# PT4115.net
KiCad netlist of a schematic drawn in EAGLE
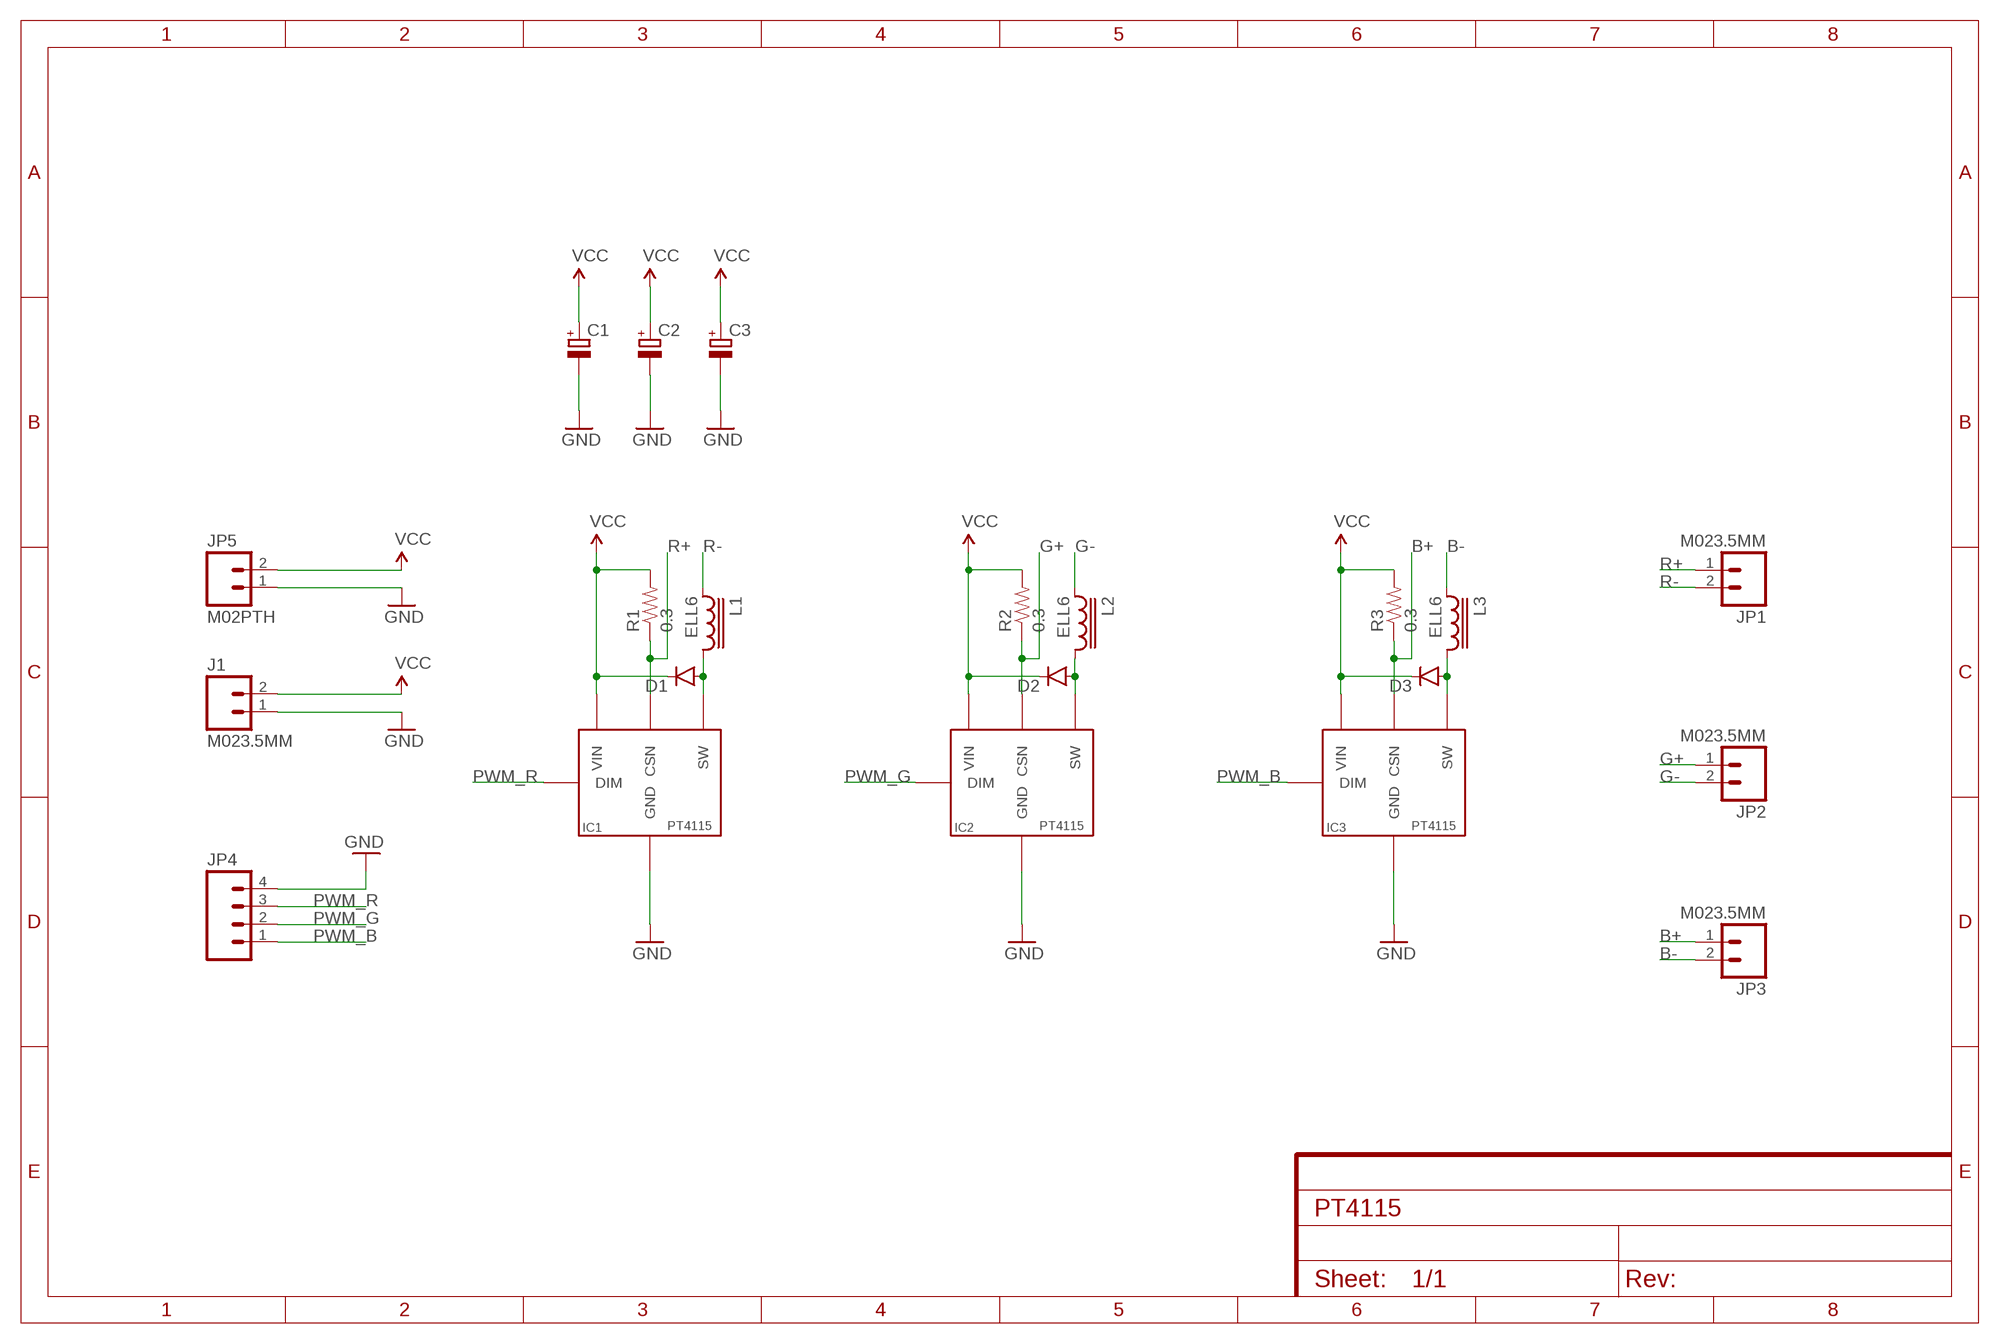
[diagram p0: schematic, sheet 1]

(export (version "E")
  (design (tool "Eeschema 10.0.6"))
  (components
    (comp (ref "C1")
      (value "CPOL-EUD/7343-31R")
      (footprint "eagle-import:D_7343-31R")
      (libsource (lib "eagle-import") (part "CPOL-EUD/7343-31R"))
    )
    (comp (ref "C2")
      (value "CPOL-EUD/7343-31R")
      (footprint "eagle-import:D_7343-31R")
      (libsource (lib "eagle-import") (part "CPOL-EUD/7343-31R"))
    )
    (comp (ref "C3")
      (value "CPOL-EUD/7343-31R")
      (footprint "eagle-import:D_7343-31R")
      (libsource (lib "eagle-import") (part "CPOL-EUD/7343-31R"))
    )
    (comp (ref "D1")
      (value "DIODESMA-KIT")
      (footprint "eagle-import:SMA-DIODE-KIT")
      (libsource (lib "eagle-import") (part "DIODESMA-KIT"))
    )
    (comp (ref "D2")
      (value "DIODESMA-KIT")
      (footprint "eagle-import:SMA-DIODE-KIT")
      (libsource (lib "eagle-import") (part "DIODESMA-KIT"))
    )
    (comp (ref "D3")
      (value "DIODESMA-KIT")
      (footprint "eagle-import:SMA-DIODE-KIT")
      (libsource (lib "eagle-import") (part "DIODESMA-KIT"))
    )
    (comp (ref "IC1")
      (value "PT4115PT4115B89E")
      (footprint "eagle-import:SOT89-5")
      (libsource (lib "eagle-import") (part "PT4115PT4115B89E"))
    )
    (comp (ref "IC2")
      (value "PT4115PT4115B89E")
      (footprint "eagle-import:SOT89-5")
      (libsource (lib "eagle-import") (part "PT4115PT4115B89E"))
    )
    (comp (ref "IC3")
      (value "PT4115PT4115B89E")
      (footprint "eagle-import:SOT89-5")
      (libsource (lib "eagle-import") (part "PT4115PT4115B89E"))
    )
    (comp (ref "J1")
      (value "M023.5MM")
      (footprint "eagle-import:SCREWTERMINAL-3.5MM-2")
      (libsource (lib "eagle-import") (part "M023.5MM"))
    )
    (comp (ref "JP1")
      (value "M023.5MM")
      (footprint "eagle-import:SCREWTERMINAL-3.5MM-2")
      (libsource (lib "eagle-import") (part "M023.5MM"))
    )
    (comp (ref "JP2")
      (value "M023.5MM")
      (footprint "eagle-import:SCREWTERMINAL-3.5MM-2")
      (libsource (lib "eagle-import") (part "M023.5MM"))
    )
    (comp (ref "JP3")
      (value "M023.5MM")
      (footprint "eagle-import:SCREWTERMINAL-3.5MM-2")
      (libsource (lib "eagle-import") (part "M023.5MM"))
    )
    (comp (ref "JP4")
      (value "M04LONGPADS")
      (footprint "eagle-import:1X04_LONGPADS")
      (libsource (lib "eagle-import") (part "M04LONGPADS"))
    )
    (comp (ref "JP5")
      (value "M02PTH")
      (footprint "eagle-import:1X02")
      (libsource (lib "eagle-import") (part "M02PTH"))
    )
    (comp (ref "L1")
      (value "ELL6")
      (footprint "eagle-import:ELL6")
      (libsource (lib "eagle-import") (part "ELL6"))
    )
    (comp (ref "L2")
      (value "ELL6")
      (footprint "eagle-import:ELL6")
      (libsource (lib "eagle-import") (part "ELL6"))
    )
    (comp (ref "L3")
      (value "ELL6")
      (footprint "eagle-import:ELL6")
      (libsource (lib "eagle-import") (part "ELL6"))
    )
    (comp (ref "R1")
      (value "0.3")
      (footprint "eagle-import:0805")
      (libsource (lib "eagle-import") (part "0.3OHM-1/8W-1%(0805)"))
    )
    (comp (ref "R2")
      (value "0.3")
      (footprint "eagle-import:0805")
      (libsource (lib "eagle-import") (part "0.3OHM-1/8W-1%(0805)"))
    )
    (comp (ref "R3")
      (value "0.3")
      (footprint "eagle-import:0805")
      (libsource (lib "eagle-import") (part "0.3OHM-1/8W-1%(0805)"))
    )
  )
  (nets
    (net (code "1") (name "/B+") (class "Default")
      (node (ref "IC3") (pin "4") (pinfunction "CSN_4") (pintype "bidirectional"))
      (node (ref "JP3") (pin "1") (pinfunction "1_1") (pintype "passive"))
      (node (ref "R3") (pin "1") (pinfunction "1_1") (pintype "passive"))
    )
    (net (code "2") (name "/B-") (class "Default")
      (node (ref "JP3") (pin "2") (pinfunction "2_2") (pintype "passive"))
      (node (ref "L3") (pin "1") (pinfunction "1_1") (pintype "passive"))
    )
    (net (code "3") (name "/G+") (class "Default")
      (node (ref "IC2") (pin "4") (pinfunction "CSN_4") (pintype "bidirectional"))
      (node (ref "JP2") (pin "1") (pinfunction "1_1") (pintype "passive"))
      (node (ref "R2") (pin "1") (pinfunction "1_1") (pintype "passive"))
    )
    (net (code "4") (name "/G-") (class "Default")
      (node (ref "JP2") (pin "2") (pinfunction "2_2") (pintype "passive"))
      (node (ref "L2") (pin "1") (pinfunction "1_1") (pintype "passive"))
    )
    (net (code "5") (name "/PWM_B") (class "Default")
      (node (ref "IC3") (pin "3") (pinfunction "DIM_3") (pintype "bidirectional"))
      (node (ref "JP4") (pin "1") (pinfunction "1_1") (pintype "passive"))
    )
    (net (code "6") (name "/PWM_G") (class "Default")
      (node (ref "IC2") (pin "3") (pinfunction "DIM_3") (pintype "bidirectional"))
      (node (ref "JP4") (pin "2") (pinfunction "2_2") (pintype "passive"))
    )
    (net (code "7") (name "/PWM_R") (class "Default")
      (node (ref "IC1") (pin "3") (pinfunction "DIM_3") (pintype "bidirectional"))
      (node (ref "JP4") (pin "3") (pinfunction "3_3") (pintype "passive"))
    )
    (net (code "8") (name "/R+") (class "Default")
      (node (ref "IC1") (pin "4") (pinfunction "CSN_4") (pintype "bidirectional"))
      (node (ref "JP1") (pin "1") (pinfunction "1_1") (pintype "passive"))
      (node (ref "R1") (pin "1") (pinfunction "1_1") (pintype "passive"))
    )
    (net (code "9") (name "/R-") (class "Default")
      (node (ref "JP1") (pin "2") (pinfunction "2_2") (pintype "passive"))
      (node (ref "L1") (pin "1") (pinfunction "1_1") (pintype "passive"))
    )
    (net (code "10") (name "GND") (class "Default")
      (node (ref "C1") (pin "-") (pinfunction "-_-") (pintype "passive"))
      (node (ref "C2") (pin "-") (pinfunction "-_-") (pintype "passive"))
      (node (ref "C3") (pin "-") (pinfunction "-_-") (pintype "passive"))
      (node (ref "IC1") (pin "2") (pinfunction "GND_2") (pintype "power_in"))
      (node (ref "IC1") (pin "2A") (pinfunction "GND_2A") (pintype "power_in"))
      (node (ref "IC2") (pin "2") (pinfunction "GND_2") (pintype "power_in"))
      (node (ref "IC2") (pin "2A") (pinfunction "GND_2A") (pintype "power_in"))
      (node (ref "IC3") (pin "2") (pinfunction "GND_2") (pintype "power_in"))
      (node (ref "IC3") (pin "2A") (pinfunction "GND_2A") (pintype "power_in"))
      (node (ref "J1") (pin "1") (pinfunction "1_1") (pintype "passive"))
      (node (ref "JP4") (pin "4") (pinfunction "4_4") (pintype "passive"))
      (node (ref "JP5") (pin "1") (pinfunction "1_1") (pintype "passive"))
    )
    (net (code "11") (name "Net-(IC1-SW)") (class "Default")
      (node (ref "D1") (pin "A") (pinfunction "A_A") (pintype "passive"))
      (node (ref "IC1") (pin "1") (pinfunction "SW_1") (pintype "bidirectional"))
      (node (ref "L1") (pin "2") (pinfunction "2_2") (pintype "passive"))
    )
    (net (code "12") (name "Net-(IC2-SW)") (class "Default")
      (node (ref "D2") (pin "A") (pinfunction "A_A") (pintype "passive"))
      (node (ref "IC2") (pin "1") (pinfunction "SW_1") (pintype "bidirectional"))
      (node (ref "L2") (pin "2") (pinfunction "2_2") (pintype "passive"))
    )
    (net (code "13") (name "Net-(IC3-SW)") (class "Default")
      (node (ref "D3") (pin "A") (pinfunction "A_A") (pintype "passive"))
      (node (ref "IC3") (pin "1") (pinfunction "SW_1") (pintype "bidirectional"))
      (node (ref "L3") (pin "2") (pinfunction "2_2") (pintype "passive"))
    )
    (net (code "14") (name "VCC") (class "Default")
      (node (ref "C1") (pin "+") (pinfunction "+_+") (pintype "passive"))
      (node (ref "C2") (pin "+") (pinfunction "+_+") (pintype "passive"))
      (node (ref "C3") (pin "+") (pinfunction "+_+") (pintype "passive"))
      (node (ref "D1") (pin "C") (pinfunction "C_C") (pintype "passive"))
      (node (ref "D2") (pin "C") (pinfunction "C_C") (pintype "passive"))
      (node (ref "D3") (pin "C") (pinfunction "C_C") (pintype "passive"))
      (node (ref "IC1") (pin "5") (pinfunction "VIN_5") (pintype "power_in"))
      (node (ref "IC2") (pin "5") (pinfunction "VIN_5") (pintype "power_in"))
      (node (ref "IC3") (pin "5") (pinfunction "VIN_5") (pintype "power_in"))
      (node (ref "J1") (pin "2") (pinfunction "2_2") (pintype "passive"))
      (node (ref "JP5") (pin "2") (pinfunction "2_2") (pintype "passive"))
      (node (ref "R1") (pin "2") (pinfunction "2_2") (pintype "passive"))
      (node (ref "R2") (pin "2") (pinfunction "2_2") (pintype "passive"))
      (node (ref "R3") (pin "2") (pinfunction "2_2") (pintype "passive"))
    )
  )
)
